# p4_esp32.net
KiCad netlist of a schematic drawn in Altium Designer
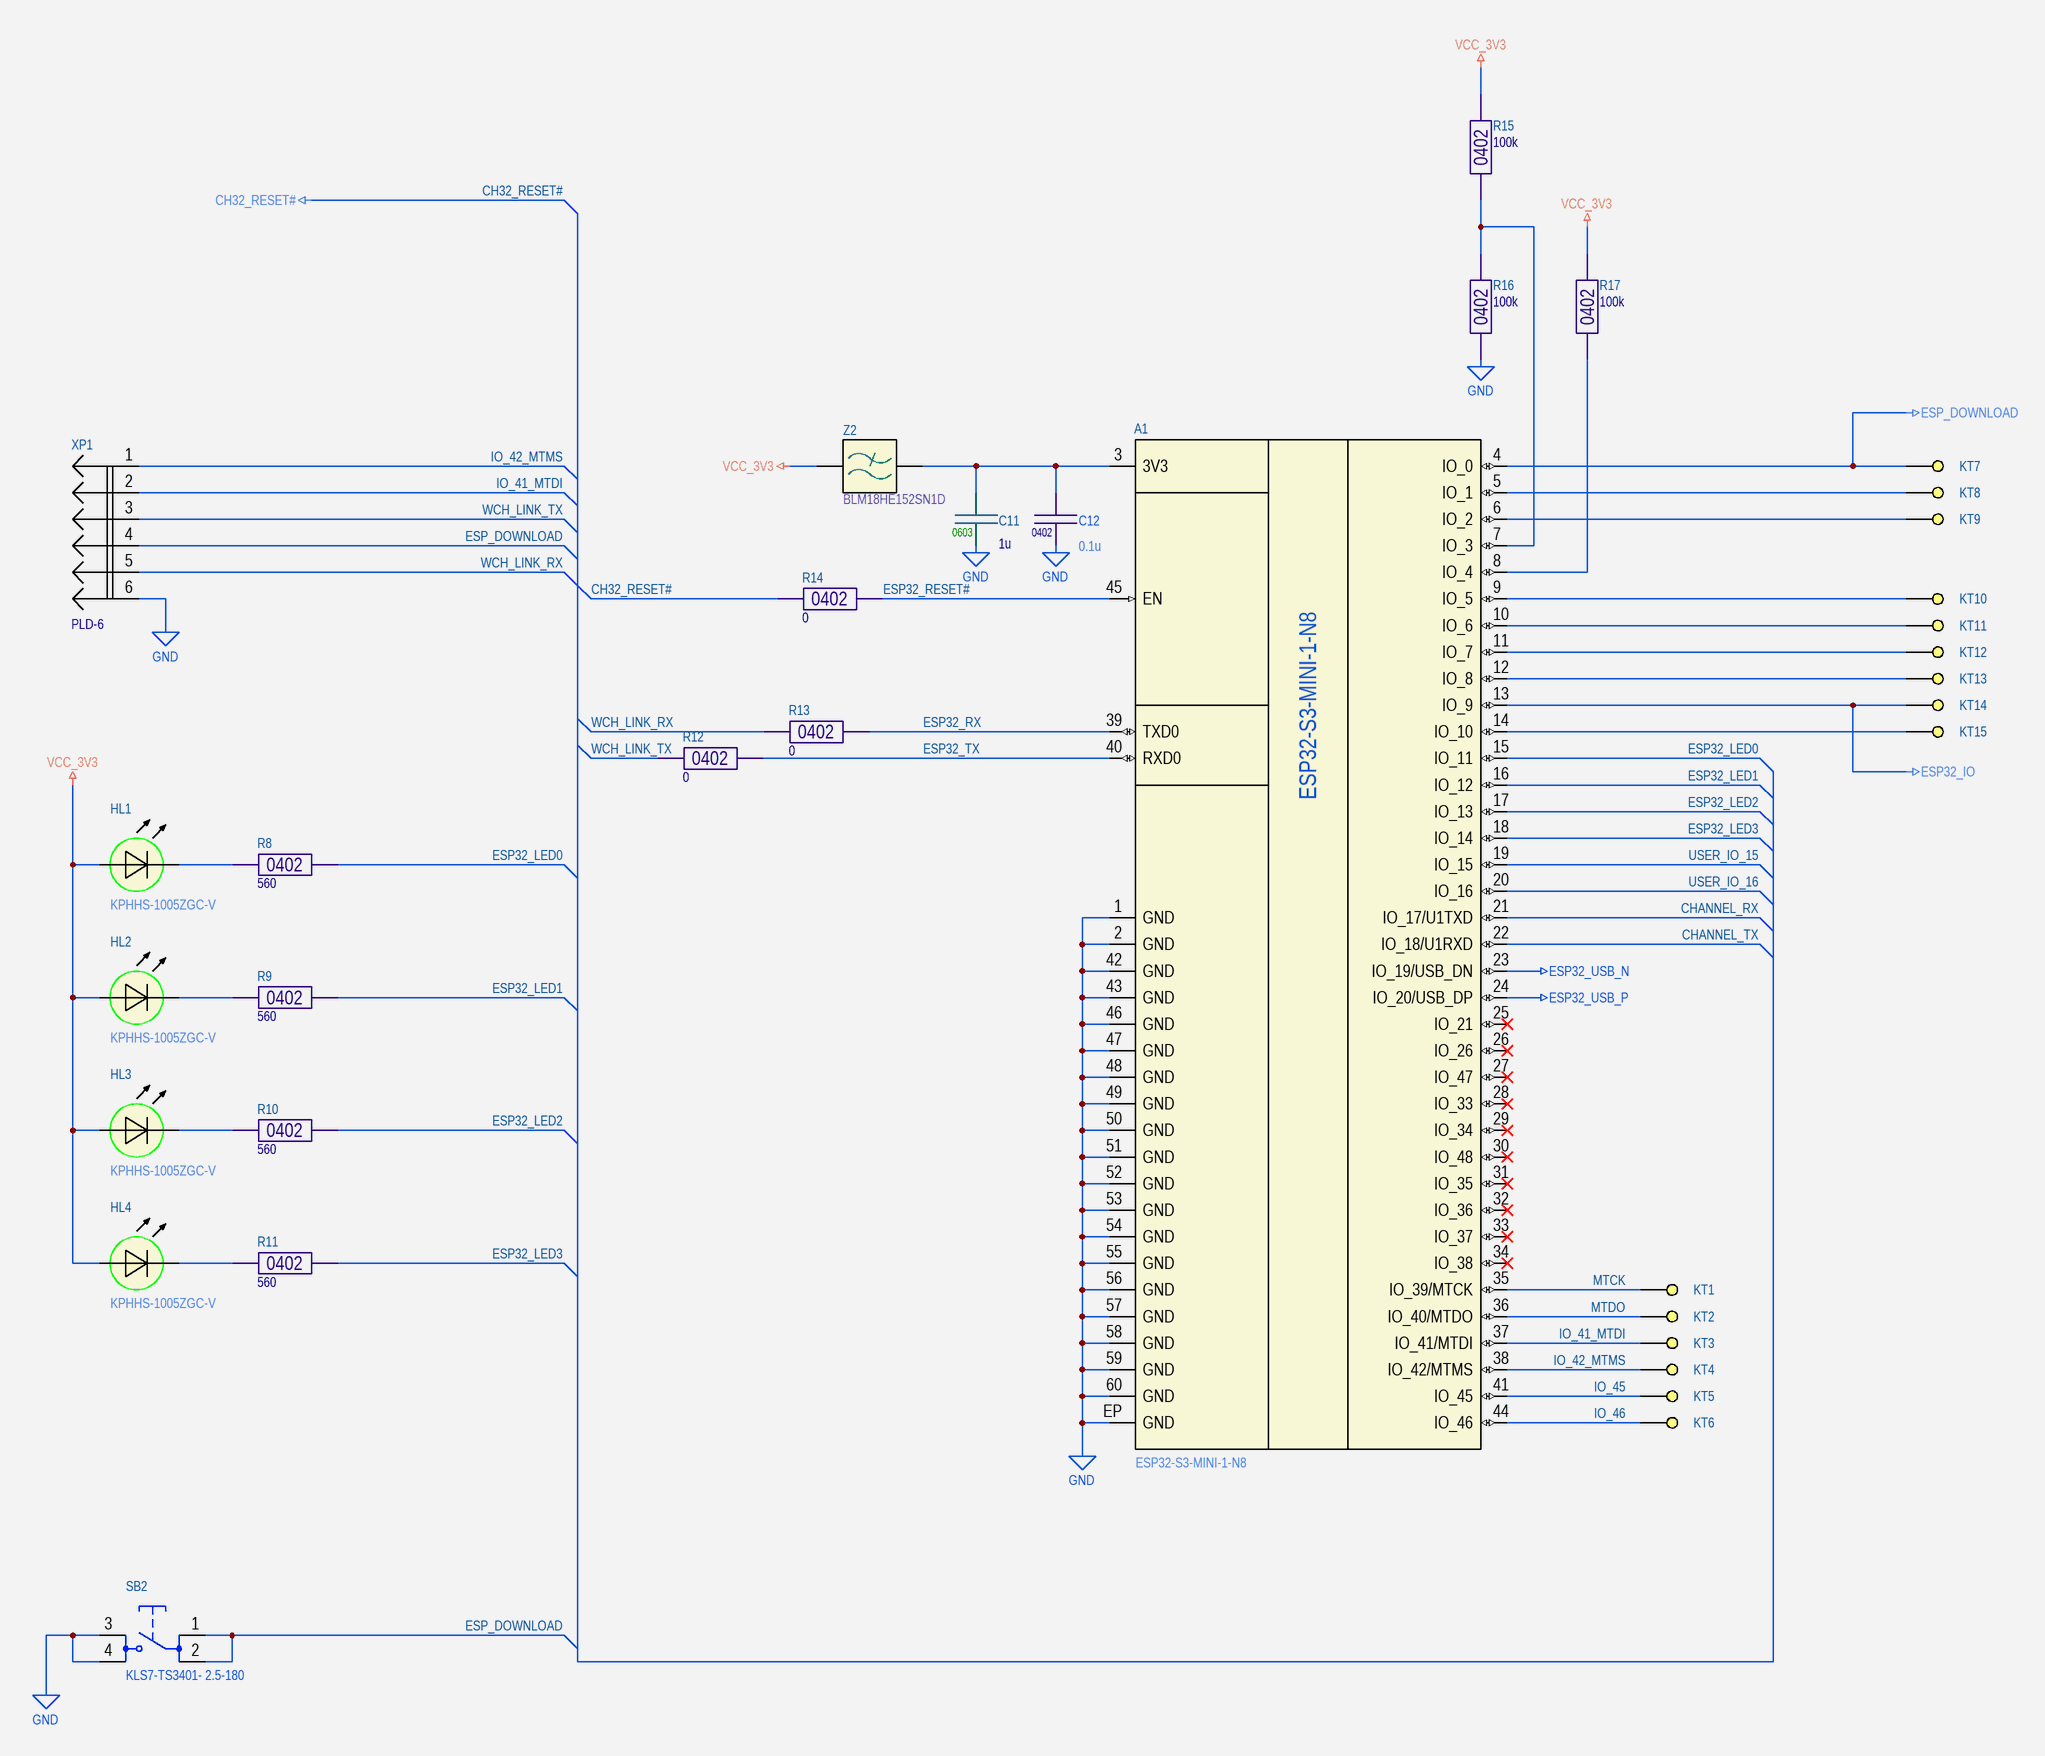
[diagram p0: p4_esp32.SchDoc]

(export (version "E")
  (design (tool "Eeschema 10.0.6"))
  (components
    (comp (ref "A1")
      (value "ESP32-S3-MINI-1-N8")
      (footprint "PcbLib_Others:ESP32-S3-MINI-1")
      (description "2.4 GHz WiFi + Bluetooth® + Bluetooth LE module")
      (fields (field (name "MANUFACTURER") "Espressif Systems"))
      (libsource (lib "Schlib_Espressif") (part "ESP32-S3-MINI-1-N8"))
    )
    (comp (ref "C11")
      (value "1u")
      (footprint "PcbLib_RC:CAP0603")
      (description "Capacitors 0603 package case")
      (fields
        (field (name "TOLERANCE") "± 20 %")
        (field (name "VOLTAGE") "6.3V")
        (field (name "PACKAGE") "0603")
      )
      (libsource (lib "Schlib_RC") (part "C0603"))
    )
    (comp (ref "C12")
      (value "0.1u")
      (footprint "PcbLib_RC:CAP0402")
      (description "Capacitors 0402 package case")
      (fields
        (field (name "TOLERANCE") "± 5 %")
        (field (name "VOLTAGE") "50 V")
        (field (name "PACKAGE") "0402")
      )
      (libsource (lib "Schlib_RC") (part "C0402"))
    )
    (comp (ref "HL1")
      (value "KPHHS-1005ZGC-V")
      (footprint "PcbLib_Others:LED0402G525")
      (description "Green led (package case 0402)")
      (fields (field (name "MANUFACTURER") "Kingbright Company LLC."))
      (libsource (lib "Schlib_Kingbright") (part "KPHHS-1005ZGC-V"))
    )
    (comp (ref "HL2")
      (value "KPHHS-1005ZGC-V")
      (footprint "PcbLib_Others:LED0402G525")
      (description "Green led (package case 0402)")
      (fields (field (name "MANUFACTURER") "Kingbright Company LLC."))
      (libsource (lib "Schlib_Kingbright") (part "KPHHS-1005ZGC-V"))
    )
    (comp (ref "HL3")
      (value "KPHHS-1005ZGC-V")
      (footprint "PcbLib_Others:LED0402G525")
      (description "Green led (package case 0402)")
      (fields (field (name "MANUFACTURER") "Kingbright Company LLC."))
      (libsource (lib "Schlib_Kingbright") (part "KPHHS-1005ZGC-V"))
    )
    (comp (ref "HL4")
      (value "KPHHS-1005ZGC-V")
      (footprint "PcbLib_Others:LED0402G525")
      (description "Green led (package case 0402)")
      (fields (field (name "MANUFACTURER") "Kingbright Company LLC."))
      (libsource (lib "Schlib_Kingbright") (part "KPHHS-1005ZGC-V"))
    )
    (comp (ref "KT1")
      (value "TEST_PAD")
      (footprint "PcbLib_Others:TEST_PAD_R1mm")
      (description "Test pad")
      (libsource (lib "Schlib_OtherComponents") (part "TEST_PAD"))
    )
    (comp (ref "KT2")
      (value "TEST_PAD")
      (footprint "PcbLib_Others:TEST_PAD_R1mm")
      (description "Test pad")
      (libsource (lib "Schlib_OtherComponents") (part "TEST_PAD"))
    )
    (comp (ref "KT3")
      (value "TEST_PAD")
      (footprint "PcbLib_Others:TEST_PAD_R1mm")
      (description "Test pad")
      (libsource (lib "Schlib_OtherComponents") (part "TEST_PAD"))
    )
    (comp (ref "KT4")
      (value "TEST_PAD")
      (footprint "PcbLib_Others:TEST_PAD_R1mm")
      (description "Test pad")
      (libsource (lib "Schlib_OtherComponents") (part "TEST_PAD"))
    )
    (comp (ref "KT5")
      (value "TEST_PAD")
      (footprint "PcbLib_Others:TEST_PAD_R1mm")
      (description "Test pad")
      (libsource (lib "Schlib_OtherComponents") (part "TEST_PAD"))
    )
    (comp (ref "KT6")
      (value "TEST_PAD")
      (footprint "PcbLib_Others:TEST_PAD_R1mm")
      (description "Test pad")
      (libsource (lib "Schlib_OtherComponents") (part "TEST_PAD"))
    )
    (comp (ref "KT7")
      (value "TEST_PAD")
      (footprint "PcbLib_Others:TEST_PAD_R1mm")
      (description "Test pad")
      (libsource (lib "Schlib_OtherComponents") (part "TEST_PAD"))
    )
    (comp (ref "KT8")
      (value "TEST_PAD")
      (footprint "PcbLib_Others:TEST_PAD_R1mm")
      (description "Test pad")
      (libsource (lib "Schlib_OtherComponents") (part "TEST_PAD"))
    )
    (comp (ref "KT9")
      (value "TEST_PAD")
      (footprint "PcbLib_Others:TEST_PAD_R1mm")
      (description "Test pad")
      (libsource (lib "Schlib_OtherComponents") (part "TEST_PAD"))
    )
    (comp (ref "KT10")
      (value "TEST_PAD")
      (footprint "PcbLib_Others:TEST_PAD_R1mm")
      (description "Test pad")
      (libsource (lib "Schlib_OtherComponents") (part "TEST_PAD"))
    )
    (comp (ref "KT11")
      (value "TEST_PAD")
      (footprint "PcbLib_Others:TEST_PAD_R1mm")
      (description "Test pad")
      (libsource (lib "Schlib_OtherComponents") (part "TEST_PAD"))
    )
    (comp (ref "KT12")
      (value "TEST_PAD")
      (footprint "PcbLib_Others:TEST_PAD_R1mm")
      (description "Test pad")
      (libsource (lib "Schlib_OtherComponents") (part "TEST_PAD"))
    )
    (comp (ref "KT13")
      (value "TEST_PAD")
      (footprint "PcbLib_Others:TEST_PAD_R1mm")
      (description "Test pad")
      (libsource (lib "Schlib_OtherComponents") (part "TEST_PAD"))
    )
    (comp (ref "KT14")
      (value "TEST_PAD")
      (footprint "PcbLib_Others:TEST_PAD_R1mm")
      (description "Test pad")
      (libsource (lib "Schlib_OtherComponents") (part "TEST_PAD"))
    )
    (comp (ref "KT15")
      (value "TEST_PAD")
      (footprint "PcbLib_Others:TEST_PAD_R1mm")
      (description "Test pad")
      (libsource (lib "Schlib_OtherComponents") (part "TEST_PAD"))
    )
    (comp (ref "R8")
      (value "560")
      (footprint "PcbLib_RC:RES0402B")
      (description "Resistor 0402 package case")
      (fields
        (field (name "TOLERANCE") "± 1 %")
        (field (name "PART NUMBER") "RC0402FR-07560RL")
        (field (name "PACKAGE") "0402")
      )
      (libsource (lib "Schlib_RC") (part "R0402"))
    )
    (comp (ref "R9")
      (value "560")
      (footprint "PcbLib_RC:RES0402B")
      (description "Resistor 0402 package case")
      (fields
        (field (name "TOLERANCE") "± 1 %")
        (field (name "PART NUMBER") "RC0402FR-07560RL")
        (field (name "PACKAGE") "0402")
      )
      (libsource (lib "Schlib_RC") (part "R0402"))
    )
    (comp (ref "R10")
      (value "560")
      (footprint "PcbLib_RC:RES0402B")
      (description "Resistor 0402 package case")
      (fields
        (field (name "TOLERANCE") "± 1 %")
        (field (name "PART NUMBER") "RC0402FR-07560RL")
        (field (name "PACKAGE") "0402")
      )
      (libsource (lib "Schlib_RC") (part "R0402"))
    )
    (comp (ref "R11")
      (value "560")
      (footprint "PcbLib_RC:RES0402B")
      (description "Resistor 0402 package case")
      (fields
        (field (name "TOLERANCE") "± 1 %")
        (field (name "PART NUMBER") "RC0402FR-07560RL")
        (field (name "PACKAGE") "0402")
      )
      (libsource (lib "Schlib_RC") (part "R0402"))
    )
    (comp (ref "R12")
      (value "0")
      (footprint "PcbLib_RC:RES0402B")
      (description "Resistor 0402 package case")
      (fields
        (field (name "TOLERANCE") "± 1 %")
        (field (name "PART NUMBER") "RC0402FR-070RL")
        (field (name "PACKAGE") "0402")
      )
      (libsource (lib "Schlib_RC") (part "R0402"))
    )
    (comp (ref "R13")
      (value "0")
      (footprint "PcbLib_RC:RES0402B")
      (description "Resistor 0402 package case")
      (fields
        (field (name "TOLERANCE") "± 1 %")
        (field (name "PART NUMBER") "RC0402FR-070RL")
        (field (name "PACKAGE") "0402")
      )
      (libsource (lib "Schlib_RC") (part "R0402"))
    )
    (comp (ref "R14")
      (value "0")
      (footprint "PcbLib_RC:RES0402B")
      (description "Resistor 0402 package case")
      (fields
        (field (name "TOLERANCE") "± 1 %")
        (field (name "PART NUMBER") "RC0402FR-070RL")
        (field (name "PACKAGE") "0402")
      )
      (libsource (lib "Schlib_RC") (part "R0402"))
    )
    (comp (ref "R15")
      (value "100k")
      (footprint "PcbLib_RC:RES0402B")
      (description "Resistor 0402 package case")
      (fields
        (field (name "TOLERANCE") "± 1 %")
        (field (name "PART NUMBER") "RC0402FR-07100KL")
        (field (name "PACKAGE") "0402")
      )
      (libsource (lib "Schlib_RC") (part "R0402"))
    )
    (comp (ref "R16")
      (value "100k")
      (footprint "PcbLib_RC:RES0402B")
      (description "Resistor 0402 package case")
      (fields
        (field (name "TOLERANCE") "± 1 %")
        (field (name "PART NUMBER") "RC0402FR-07100KL")
        (field (name "PACKAGE") "0402")
      )
      (libsource (lib "Schlib_RC") (part "R0402"))
    )
    (comp (ref "R17")
      (value "100k")
      (footprint "PcbLib_RC:RES0402B")
      (description "Resistor 0402 package case")
      (fields
        (field (name "TOLERANCE") "± 1 %")
        (field (name "PART NUMBER") "RC0402FR-07100KL")
        (field (name "PACKAGE") "0402")
      )
      (libsource (lib "Schlib_RC") (part "R0402"))
    )
    (comp (ref "SB2")
      (value "KLS7-TS3401- 2.5-180")
      (footprint "PcbLib_Others:TVAF11")
      (description "Tact Button SMD 4х3х2.5mm")
      (fields (field (name "MANUFACTURER") "KLS"))
      (libsource (lib "Schlib_OtherComponents") (part "TVAF11"))
    )
    (comp (ref "XP1")
      (value "PLD-6")
      (footprint "PcbLib_Pin_Headers:PLD-6")
      (libsource (lib "Schlib_Pin_Headers") (part "PLD-6"))
    )
    (comp (ref "Z2")
      (value "BLM18HE152SN1D")
      (footprint "PcbLib_RC:BLM0603C")
      (description "Power line filter, imperdance 1500 Ohm @100MHz (current 0.5A)")
      (fields (field (name "MANUFACTURER") "Murata"))
      (libsource (lib "Schlib_Murata") (part "BLM18HE152SN1D"))
    )
  )
  (nets
    (net (code "1") (name "/CHANNEL_RX") (class "Default")
      (node (ref "A1") (pin "21") (pinfunction "IO_17/U1TXD_21") (pintype "bidirectional"))
    )
    (net (code "2") (name "/CHANNEL_TX") (class "Default")
      (node (ref "A1") (pin "22") (pinfunction "IO_18/U1RXD_22") (pintype "bidirectional"))
    )
    (net (code "3") (name "/ESP32_LED0") (class "Default")
      (node (ref "A1") (pin "15") (pinfunction "IO_11_15") (pintype "bidirectional"))
      (node (ref "R8") (pin "2") (pinfunction "2_2") (pintype "passive"))
    )
    (net (code "4") (name "/ESP32_LED1") (class "Default")
      (node (ref "A1") (pin "16") (pinfunction "IO_12_16") (pintype "bidirectional"))
      (node (ref "R9") (pin "2") (pinfunction "2_2") (pintype "passive"))
    )
    (net (code "5") (name "/ESP32_LED2") (class "Default")
      (node (ref "A1") (pin "17") (pinfunction "IO_13_17") (pintype "bidirectional"))
      (node (ref "R10") (pin "2") (pinfunction "2_2") (pintype "passive"))
    )
    (net (code "6") (name "/ESP32_LED3") (class "Default")
      (node (ref "A1") (pin "18") (pinfunction "IO_14_18") (pintype "bidirectional"))
      (node (ref "R11") (pin "2") (pinfunction "2_2") (pintype "passive"))
    )
    (net (code "7") (name "/ESP32_RESET#") (class "Default")
      (node (ref "A1") (pin "45") (pinfunction "EN_45") (pintype "input"))
      (node (ref "R14") (pin "1") (pinfunction "1_1") (pintype "passive"))
    )
    (net (code "8") (name "/ESP32_RX") (class "Default")
      (node (ref "A1") (pin "39") (pinfunction "TXD0_39") (pintype "bidirectional"))
      (node (ref "R13") (pin "2") (pinfunction "2_2") (pintype "passive"))
    )
    (net (code "9") (name "/ESP32_TX") (class "Default")
      (node (ref "A1") (pin "40") (pinfunction "RXD0_40") (pintype "bidirectional"))
      (node (ref "R12") (pin "2") (pinfunction "2_2") (pintype "passive"))
    )
    (net (code "10") (name "/IO_41_MTDI") (class "Default")
      (node (ref "A1") (pin "37") (pinfunction "IO_41/MTDI_37") (pintype "bidirectional"))
      (node (ref "KT3") (pin "1") (pinfunction "1_1") (pintype "passive"))
      (node (ref "XP1") (pin "2") (pinfunction "2_2") (pintype "passive"))
    )
    (net (code "11") (name "/IO_42_MTMS") (class "Default")
      (node (ref "A1") (pin "38") (pinfunction "IO_42/MTMS_38") (pintype "bidirectional"))
      (node (ref "KT4") (pin "1") (pinfunction "1_1") (pintype "passive"))
      (node (ref "XP1") (pin "1") (pinfunction "1_1") (pintype "passive"))
    )
    (net (code "12") (name "/IO_45") (class "Default")
      (node (ref "A1") (pin "41") (pinfunction "IO_45_41") (pintype "bidirectional"))
      (node (ref "KT5") (pin "1") (pinfunction "1_1") (pintype "passive"))
    )
    (net (code "13") (name "/IO_46") (class "Default")
      (node (ref "A1") (pin "44") (pinfunction "IO_46_44") (pintype "bidirectional"))
      (node (ref "KT6") (pin "1") (pinfunction "1_1") (pintype "passive"))
    )
    (net (code "14") (name "/MTCK") (class "Default")
      (node (ref "A1") (pin "35") (pinfunction "IO_39/MTCK_35") (pintype "bidirectional"))
      (node (ref "KT1") (pin "1") (pinfunction "1_1") (pintype "passive"))
    )
    (net (code "15") (name "/MTDO") (class "Default")
      (node (ref "A1") (pin "36") (pinfunction "IO_40/MTDO_36") (pintype "bidirectional"))
      (node (ref "KT2") (pin "1") (pinfunction "1_1") (pintype "passive"))
    )
    (net (code "16") (name "/USER_IO_15") (class "Default")
      (node (ref "A1") (pin "19") (pinfunction "IO_15_19") (pintype "bidirectional"))
    )
    (net (code "17") (name "/USER_IO_16") (class "Default")
      (node (ref "A1") (pin "20") (pinfunction "IO_16_20") (pintype "bidirectional"))
    )
    (net (code "18") (name "/WCH_LINK_RX") (class "Default")
      (node (ref "R13") (pin "1") (pinfunction "1_1") (pintype "passive"))
      (node (ref "XP1") (pin "5") (pinfunction "5_5") (pintype "passive"))
    )
    (net (code "19") (name "/WCH_LINK_TX") (class "Default")
      (node (ref "R12") (pin "1") (pinfunction "1_1") (pintype "passive"))
      (node (ref "XP1") (pin "3") (pinfunction "3_3") (pintype "passive"))
    )
    (net (code "20") (name "CH32_RESET#") (class "Default")
      (node (ref "R14") (pin "2") (pinfunction "2_2") (pintype "passive"))
    )
    (net (code "21") (name "ESP32_IO") (class "Default")
      (node (ref "A1") (pin "13") (pinfunction "IO_9_13") (pintype "bidirectional"))
      (node (ref "KT14") (pin "1") (pinfunction "1_1") (pintype "passive"))
    )
    (net (code "22") (name "ESP32_USB_N") (class "Default")
      (node (ref "A1") (pin "23") (pinfunction "IO_19/USB_DN_23") (pintype "bidirectional"))
    )
    (net (code "23") (name "ESP32_USB_P") (class "Default")
      (node (ref "A1") (pin "24") (pinfunction "IO_20/USB_DP_24") (pintype "bidirectional"))
    )
    (net (code "24") (name "ESP_DOWNLOAD") (class "Default")
      (node (ref "A1") (pin "4") (pinfunction "IO_0_4") (pintype "bidirectional"))
      (node (ref "KT7") (pin "1") (pinfunction "1_1") (pintype "passive"))
      (node (ref "SB2") (pin "1") (pinfunction "1_1") (pintype "passive"))
      (node (ref "SB2") (pin "2") (pinfunction "2_2") (pintype "passive"))
      (node (ref "XP1") (pin "4") (pinfunction "4_4") (pintype "passive"))
    )
    (net (code "25") (name "GND") (class "Default")
      (node (ref "A1") (pin "1") (pinfunction "GND_1") (pintype "power_in"))
      (node (ref "A1") (pin "2") (pinfunction "GND_2") (pintype "power_in"))
      (node (ref "A1") (pin "42") (pinfunction "GND_42") (pintype "power_in"))
      (node (ref "A1") (pin "43") (pinfunction "GND_43") (pintype "power_in"))
      (node (ref "A1") (pin "46") (pinfunction "GND_46") (pintype "power_in"))
      (node (ref "A1") (pin "47") (pinfunction "GND_47") (pintype "power_in"))
      (node (ref "A1") (pin "48") (pinfunction "GND_48") (pintype "power_in"))
      (node (ref "A1") (pin "49") (pinfunction "GND_49") (pintype "power_in"))
      (node (ref "A1") (pin "50") (pinfunction "GND_50") (pintype "power_in"))
      (node (ref "A1") (pin "51") (pinfunction "GND_51") (pintype "power_in"))
      (node (ref "A1") (pin "52") (pinfunction "GND_52") (pintype "power_in"))
      (node (ref "A1") (pin "53") (pinfunction "GND_53") (pintype "power_in"))
      (node (ref "A1") (pin "54") (pinfunction "GND_54") (pintype "power_in"))
      (node (ref "A1") (pin "55") (pinfunction "GND_55") (pintype "power_in"))
      (node (ref "A1") (pin "56") (pinfunction "GND_56") (pintype "power_in"))
      (node (ref "A1") (pin "57") (pinfunction "GND_57") (pintype "power_in"))
      (node (ref "A1") (pin "58") (pinfunction "GND_58") (pintype "power_in"))
      (node (ref "A1") (pin "59") (pinfunction "GND_59") (pintype "power_in"))
      (node (ref "A1") (pin "60") (pinfunction "GND_60") (pintype "power_in"))
      (node (ref "A1") (pin "EP") (pinfunction "GND_EP") (pintype "power_in"))
      (node (ref "C11") (pin "1") (pinfunction "1_1") (pintype "passive"))
      (node (ref "C12") (pin "2") (pinfunction "2_2") (pintype "passive"))
      (node (ref "R16") (pin "2") (pinfunction "2_2") (pintype "passive"))
      (node (ref "SB2") (pin "3") (pinfunction "3_3") (pintype "passive"))
      (node (ref "SB2") (pin "4") (pinfunction "4_4") (pintype "passive"))
      (node (ref "XP1") (pin "6") (pinfunction "6_6") (pintype "passive"))
    )
    (net (code "26") (name "Net-(A1-3V3)") (class "Default")
      (node (ref "A1") (pin "3") (pinfunction "3V3_3") (pintype "power_in"))
      (node (ref "C11") (pin "2") (pinfunction "2_2") (pintype "passive"))
      (node (ref "C12") (pin "1") (pinfunction "1_1") (pintype "passive"))
      (node (ref "Z2") (pin "1") (pinfunction "1_1") (pintype "passive"))
    )
    (net (code "27") (name "Net-(A1-IO_1)") (class "Default")
      (node (ref "A1") (pin "5") (pinfunction "IO_1_5") (pintype "bidirectional"))
      (node (ref "KT8") (pin "1") (pinfunction "1_1") (pintype "passive"))
    )
    (net (code "28") (name "Net-(A1-IO_2)") (class "Default")
      (node (ref "A1") (pin "6") (pinfunction "IO_2_6") (pintype "bidirectional"))
      (node (ref "KT9") (pin "1") (pinfunction "1_1") (pintype "passive"))
    )
    (net (code "29") (name "Net-(A1-IO_3)") (class "Default")
      (node (ref "A1") (pin "7") (pinfunction "IO_3_7") (pintype "bidirectional"))
      (node (ref "R15") (pin "2") (pinfunction "2_2") (pintype "passive"))
      (node (ref "R16") (pin "1") (pinfunction "1_1") (pintype "passive"))
    )
    (net (code "30") (name "Net-(A1-IO_4)") (class "Default")
      (node (ref "A1") (pin "8") (pinfunction "IO_4_8") (pintype "bidirectional"))
      (node (ref "R17") (pin "2") (pinfunction "2_2") (pintype "passive"))
    )
    (net (code "31") (name "Net-(A1-IO_5)") (class "Default")
      (node (ref "A1") (pin "9") (pinfunction "IO_5_9") (pintype "bidirectional"))
      (node (ref "KT10") (pin "1") (pinfunction "1_1") (pintype "passive"))
    )
    (net (code "32") (name "Net-(A1-IO_6)") (class "Default")
      (node (ref "A1") (pin "10") (pinfunction "IO_6_10") (pintype "bidirectional"))
      (node (ref "KT11") (pin "1") (pinfunction "1_1") (pintype "passive"))
    )
    (net (code "33") (name "Net-(A1-IO_7)") (class "Default")
      (node (ref "A1") (pin "11") (pinfunction "IO_7_11") (pintype "bidirectional"))
      (node (ref "KT12") (pin "1") (pinfunction "1_1") (pintype "passive"))
    )
    (net (code "34") (name "Net-(A1-IO_8)") (class "Default")
      (node (ref "A1") (pin "12") (pinfunction "IO_8_12") (pintype "bidirectional"))
      (node (ref "KT13") (pin "1") (pinfunction "1_1") (pintype "passive"))
    )
    (net (code "35") (name "Net-(A1-IO_10)") (class "Default")
      (node (ref "A1") (pin "14") (pinfunction "IO_10_14") (pintype "bidirectional"))
      (node (ref "KT15") (pin "1") (pinfunction "1_1") (pintype "passive"))
    )
    (net (code "36") (name "Net-(HL1-Pad1)") (class "Default")
      (node (ref "HL1") (pin "1") (pinfunction "1_1") (pintype "passive"))
      (node (ref "R8") (pin "1") (pinfunction "1_1") (pintype "passive"))
    )
    (net (code "37") (name "Net-(HL2-Pad1)") (class "Default")
      (node (ref "HL2") (pin "1") (pinfunction "1_1") (pintype "passive"))
      (node (ref "R9") (pin "1") (pinfunction "1_1") (pintype "passive"))
    )
    (net (code "38") (name "Net-(HL3-Pad1)") (class "Default")
      (node (ref "HL3") (pin "1") (pinfunction "1_1") (pintype "passive"))
      (node (ref "R10") (pin "1") (pinfunction "1_1") (pintype "passive"))
    )
    (net (code "39") (name "Net-(HL4-Pad1)") (class "Default")
      (node (ref "HL4") (pin "1") (pinfunction "1_1") (pintype "passive"))
      (node (ref "R11") (pin "1") (pinfunction "1_1") (pintype "passive"))
    )
    (net (code "40") (name "VCC_3V3") (class "Default")
      (node (ref "HL1") (pin "2") (pinfunction "2_2") (pintype "passive"))
      (node (ref "HL2") (pin "2") (pinfunction "2_2") (pintype "passive"))
      (node (ref "HL3") (pin "2") (pinfunction "2_2") (pintype "passive"))
      (node (ref "HL4") (pin "2") (pinfunction "2_2") (pintype "passive"))
      (node (ref "R15") (pin "1") (pinfunction "1_1") (pintype "passive"))
      (node (ref "R17") (pin "1") (pinfunction "1_1") (pintype "passive"))
      (node (ref "Z2") (pin "2") (pinfunction "2_2") (pintype "passive"))
    )
    (net (code "41") (name "unconnected-(A1-IO_21-Pad25)") (class "Default")
      (node (ref "A1") (pin "25") (pinfunction "IO_21_25") (pintype "bidirectional+no_connect"))
    )
    (net (code "42") (name "unconnected-(A1-IO_26-Pad26)") (class "Default")
      (node (ref "A1") (pin "26") (pinfunction "IO_26_26") (pintype "bidirectional+no_connect"))
    )
    (net (code "43") (name "unconnected-(A1-IO_33-Pad28)") (class "Default")
      (node (ref "A1") (pin "28") (pinfunction "IO_33_28") (pintype "bidirectional+no_connect"))
    )
    (net (code "44") (name "unconnected-(A1-IO_34-Pad29)") (class "Default")
      (node (ref "A1") (pin "29") (pinfunction "IO_34_29") (pintype "bidirectional+no_connect"))
    )
    (net (code "45") (name "unconnected-(A1-IO_35-Pad31)") (class "Default")
      (node (ref "A1") (pin "31") (pinfunction "IO_35_31") (pintype "bidirectional+no_connect"))
    )
    (net (code "46") (name "unconnected-(A1-IO_36-Pad32)") (class "Default")
      (node (ref "A1") (pin "32") (pinfunction "IO_36_32") (pintype "bidirectional+no_connect"))
    )
    (net (code "47") (name "unconnected-(A1-IO_37-Pad33)") (class "Default")
      (node (ref "A1") (pin "33") (pinfunction "IO_37_33") (pintype "bidirectional+no_connect"))
    )
    (net (code "48") (name "unconnected-(A1-IO_38-Pad34)") (class "Default")
      (node (ref "A1") (pin "34") (pinfunction "IO_38_34") (pintype "bidirectional+no_connect"))
    )
    (net (code "49") (name "unconnected-(A1-IO_47-Pad27)") (class "Default")
      (node (ref "A1") (pin "27") (pinfunction "IO_47_27") (pintype "bidirectional+no_connect"))
    )
    (net (code "50") (name "unconnected-(A1-IO_48-Pad30)") (class "Default")
      (node (ref "A1") (pin "30") (pinfunction "IO_48_30") (pintype "bidirectional+no_connect"))
    )
  )
)
